# LED4.net
KiCad netlist of a schematic drawn in Altium Designer
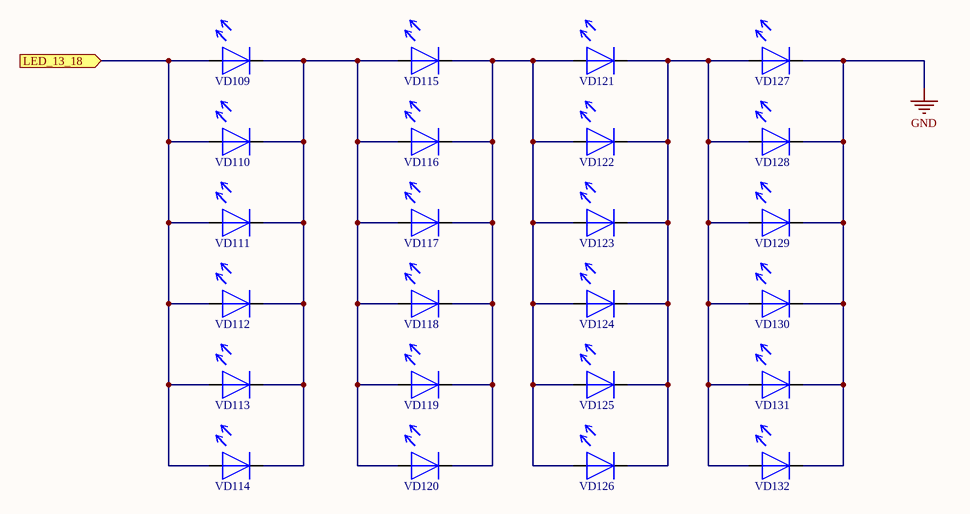
[diagram p0: LED4.SchDoc]

(export (version "E")
  (design (tool "Eeschema 10.0.6"))
  (components
    (comp (ref "VD109")
      (value "SPMWHT541MD5WAT0SB")
      (footprint "LED_Samsung")
      (libsource (lib "gprs_modem_2") (part "LED SPMWHT541MD5WAT0SB"))
    )
    (comp (ref "VD110")
      (value "SPMWHT541MD5WAT0SB")
      (footprint "LED_Samsung")
      (libsource (lib "gprs_modem_2") (part "LED SPMWHT541MD5WAT0SB"))
    )
    (comp (ref "VD111")
      (value "SPMWHT541MD5WAT0SB")
      (footprint "LED_Samsung")
      (libsource (lib "gprs_modem_2") (part "LED SPMWHT541MD5WAT0SB"))
    )
    (comp (ref "VD112")
      (value "SPMWHT541MD5WAT0SB")
      (footprint "LED_Samsung")
      (libsource (lib "gprs_modem_2") (part "LED SPMWHT541MD5WAT0SB"))
    )
    (comp (ref "VD113")
      (value "SPMWHT541MD5WAT0SB")
      (footprint "LED_Samsung")
      (libsource (lib "gprs_modem_2") (part "LED SPMWHT541MD5WAT0SB"))
    )
    (comp (ref "VD114")
      (value "SPMWHT541MD5WAT0SB")
      (footprint "LED_Samsung")
      (libsource (lib "gprs_modem_2") (part "LED SPMWHT541MD5WAT0SB"))
    )
    (comp (ref "VD115")
      (value "SPMWHT541MD5WAT0SB")
      (footprint "LED_Samsung")
      (libsource (lib "gprs_modem_2") (part "LED SPMWHT541MD5WAT0SB"))
    )
    (comp (ref "VD116")
      (value "SPMWHT541MD5WAT0SB")
      (footprint "LED_Samsung")
      (libsource (lib "gprs_modem_2") (part "LED SPMWHT541MD5WAT0SB"))
    )
    (comp (ref "VD117")
      (value "SPMWHT541MD5WAT0SB")
      (footprint "LED_Samsung")
      (libsource (lib "gprs_modem_2") (part "LED SPMWHT541MD5WAT0SB"))
    )
    (comp (ref "VD118")
      (value "SPMWHT541MD5WAT0SB")
      (footprint "LED_Samsung")
      (libsource (lib "gprs_modem_2") (part "LED SPMWHT541MD5WAT0SB"))
    )
    (comp (ref "VD119")
      (value "SPMWHT541MD5WAT0SB")
      (footprint "LED_Samsung")
      (libsource (lib "gprs_modem_2") (part "LED SPMWHT541MD5WAT0SB"))
    )
    (comp (ref "VD120")
      (value "SPMWHT541MD5WAT0SB")
      (footprint "LED_Samsung")
      (libsource (lib "gprs_modem_2") (part "LED SPMWHT541MD5WAT0SB"))
    )
    (comp (ref "VD121")
      (value "SPMWHT541MD5WAT0SB")
      (footprint "LED_Samsung")
      (libsource (lib "gprs_modem_2") (part "LED SPMWHT541MD5WAT0SB"))
    )
    (comp (ref "VD122")
      (value "SPMWHT541MD5WAT0SB")
      (footprint "LED_Samsung")
      (libsource (lib "gprs_modem_2") (part "LED SPMWHT541MD5WAT0SB"))
    )
    (comp (ref "VD123")
      (value "SPMWHT541MD5WAT0SB")
      (footprint "LED_Samsung")
      (libsource (lib "gprs_modem_2") (part "LED SPMWHT541MD5WAT0SB"))
    )
    (comp (ref "VD124")
      (value "SPMWHT541MD5WAT0SB")
      (footprint "LED_Samsung")
      (libsource (lib "gprs_modem_2") (part "LED SPMWHT541MD5WAT0SB"))
    )
    (comp (ref "VD125")
      (value "SPMWHT541MD5WAT0SB")
      (footprint "LED_Samsung")
      (libsource (lib "gprs_modem_2") (part "LED SPMWHT541MD5WAT0SB"))
    )
    (comp (ref "VD126")
      (value "SPMWHT541MD5WAT0SB")
      (footprint "LED_Samsung")
      (libsource (lib "gprs_modem_2") (part "LED SPMWHT541MD5WAT0SB"))
    )
    (comp (ref "VD127")
      (value "SPMWHT541MD5WAT0SB")
      (footprint "LED_Samsung")
      (libsource (lib "gprs_modem_2") (part "LED SPMWHT541MD5WAT0SB"))
    )
    (comp (ref "VD128")
      (value "SPMWHT541MD5WAT0SB")
      (footprint "LED_Samsung")
      (libsource (lib "gprs_modem_2") (part "LED SPMWHT541MD5WAT0SB"))
    )
    (comp (ref "VD129")
      (value "SPMWHT541MD5WAT0SB")
      (footprint "LED_Samsung")
      (libsource (lib "gprs_modem_2") (part "LED SPMWHT541MD5WAT0SB"))
    )
    (comp (ref "VD130")
      (value "SPMWHT541MD5WAT0SB")
      (footprint "LED_Samsung")
      (libsource (lib "gprs_modem_2") (part "LED SPMWHT541MD5WAT0SB"))
    )
    (comp (ref "VD131")
      (value "SPMWHT541MD5WAT0SB")
      (footprint "LED_Samsung")
      (libsource (lib "gprs_modem_2") (part "LED SPMWHT541MD5WAT0SB"))
    )
    (comp (ref "VD132")
      (value "SPMWHT541MD5WAT0SB")
      (footprint "LED_Samsung")
      (libsource (lib "gprs_modem_2") (part "LED SPMWHT541MD5WAT0SB"))
    )
  )
  (nets
    (net (code "1") (name "/LED_13_18") (class "Default")
      (node (ref "VD109") (pin "1") (pintype "passive"))
      (node (ref "VD110") (pin "1") (pintype "passive"))
      (node (ref "VD111") (pin "1") (pintype "passive"))
      (node (ref "VD112") (pin "1") (pintype "passive"))
      (node (ref "VD113") (pin "1") (pintype "passive"))
      (node (ref "VD114") (pin "1") (pintype "passive"))
    )
    (net (code "2") (name "GND") (class "Default")
      (node (ref "VD127") (pin "2") (pintype "passive"))
      (node (ref "VD128") (pin "2") (pintype "passive"))
      (node (ref "VD129") (pin "2") (pintype "passive"))
      (node (ref "VD130") (pin "2") (pintype "passive"))
      (node (ref "VD131") (pin "2") (pintype "passive"))
      (node (ref "VD132") (pin "2") (pintype "passive"))
    )
    (net (code "3") (name "Net-(VD109-Pad2)") (class "Default")
      (node (ref "VD109") (pin "2") (pintype "passive"))
      (node (ref "VD110") (pin "2") (pintype "passive"))
      (node (ref "VD111") (pin "2") (pintype "passive"))
      (node (ref "VD112") (pin "2") (pintype "passive"))
      (node (ref "VD113") (pin "2") (pintype "passive"))
      (node (ref "VD114") (pin "2") (pintype "passive"))
      (node (ref "VD115") (pin "1") (pintype "passive"))
      (node (ref "VD116") (pin "1") (pintype "passive"))
      (node (ref "VD117") (pin "1") (pintype "passive"))
      (node (ref "VD118") (pin "1") (pintype "passive"))
      (node (ref "VD119") (pin "1") (pintype "passive"))
      (node (ref "VD120") (pin "1") (pintype "passive"))
    )
    (net (code "4") (name "Net-(VD115-Pad2)") (class "Default")
      (node (ref "VD115") (pin "2") (pintype "passive"))
      (node (ref "VD116") (pin "2") (pintype "passive"))
      (node (ref "VD117") (pin "2") (pintype "passive"))
      (node (ref "VD118") (pin "2") (pintype "passive"))
      (node (ref "VD119") (pin "2") (pintype "passive"))
      (node (ref "VD120") (pin "2") (pintype "passive"))
      (node (ref "VD121") (pin "1") (pintype "passive"))
      (node (ref "VD122") (pin "1") (pintype "passive"))
      (node (ref "VD123") (pin "1") (pintype "passive"))
      (node (ref "VD124") (pin "1") (pintype "passive"))
      (node (ref "VD125") (pin "1") (pintype "passive"))
      (node (ref "VD126") (pin "1") (pintype "passive"))
    )
    (net (code "5") (name "Net-(VD121-Pad2)") (class "Default")
      (node (ref "VD121") (pin "2") (pintype "passive"))
      (node (ref "VD122") (pin "2") (pintype "passive"))
      (node (ref "VD123") (pin "2") (pintype "passive"))
      (node (ref "VD124") (pin "2") (pintype "passive"))
      (node (ref "VD125") (pin "2") (pintype "passive"))
      (node (ref "VD126") (pin "2") (pintype "passive"))
      (node (ref "VD127") (pin "1") (pintype "passive"))
      (node (ref "VD128") (pin "1") (pintype "passive"))
      (node (ref "VD129") (pin "1") (pintype "passive"))
      (node (ref "VD130") (pin "1") (pintype "passive"))
      (node (ref "VD131") (pin "1") (pintype "passive"))
      (node (ref "VD132") (pin "1") (pintype "passive"))
    )
  )
)
